# skill_test.net
KiCad netlist of a schematic drawn in EAGLE
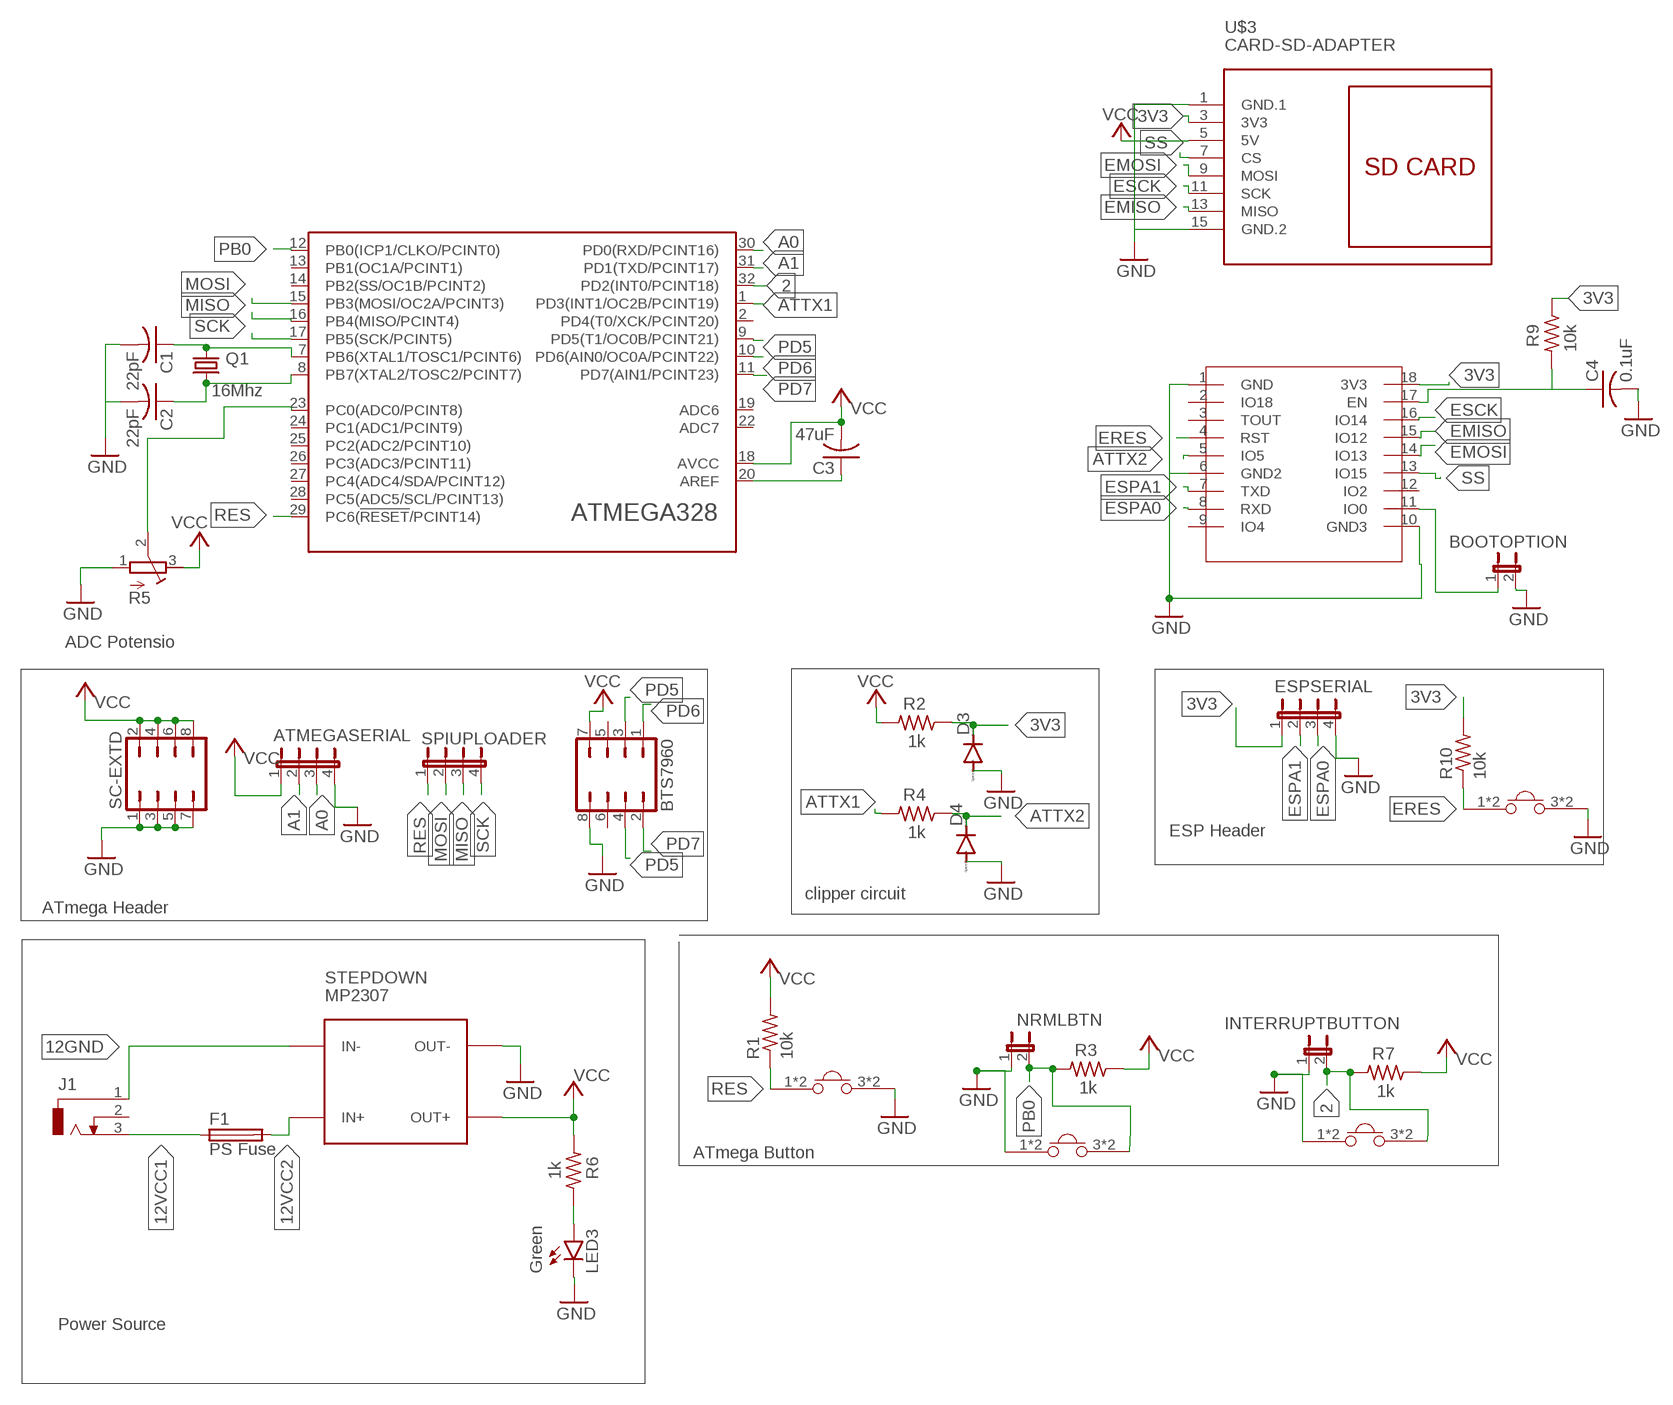
[diagram p0: schematic, sheet 1]

(export (version "E")
  (design (tool "Eeschema 10.0.6"))
  (components
    (comp (ref "2")
      (value "SMD-PUSHBUTTON")
      (footprint "eagle-import:SMD-PUSHBUTTON")
      (libsource (lib "eagle-import") (part "SMD-PUSHBUTTON"))
    )
    (comp (ref "ATMEGA328")
      (value "ATMEGA48/88/168/328-AU")
      (footprint "eagle-import:TQFP32-08")
      (libsource (lib "eagle-import") (part "ATMEGA48/88/168/328-AU"))
    )
    (comp (ref "ATMEGASERIAL")
      (value "JP4E")
      (footprint "eagle-import:JP4")
      (libsource (lib "eagle-import") (part "JP4E"))
    )
    (comp (ref "BOOTOPTION")
      (value "JP1E")
      (footprint "eagle-import:JP1")
      (libsource (lib "eagle-import") (part "JP1E"))
    )
    (comp (ref "BTS7960")
      (value "JP4Q")
      (footprint "eagle-import:JP4Q")
      (libsource (lib "eagle-import") (part "JP4Q"))
    )
    (comp (ref "C1")
      (value "22pF")
      (footprint "eagle-import:C0805")
      (libsource (lib "eagle-import") (part "C-USC0805"))
    )
    (comp (ref "C2")
      (value "22pF")
      (footprint "eagle-import:C0805")
      (libsource (lib "eagle-import") (part "C-USC0805"))
    )
    (comp (ref "C3")
      (value "47uF")
      (footprint "eagle-import:C0805")
      (libsource (lib "eagle-import") (part "C-USC0805"))
    )
    (comp (ref "C4")
      (value "0.1uF")
      (footprint "eagle-import:C025-024X044")
      (libsource (lib "eagle-import") (part "C-US025-024X044"))
    )
    (comp (ref "D3")
      (value "BAT81")
      (footprint "eagle-import:DO34-7")
      (libsource (lib "eagle-import") (part "BAT81"))
    )
    (comp (ref "D4")
      (value "BAT81")
      (footprint "eagle-import:DO34-7")
      (libsource (lib "eagle-import") (part "BAT81"))
    )
    (comp (ref "ESPSERIAL")
      (value "JP4E")
      (footprint "eagle-import:JP4")
      (libsource (lib "eagle-import") (part "JP4E"))
    )
    (comp (ref "F1")
      (value "PS Fuse")
      (footprint "eagle-import:FUSE_HOLDER_5X20MM")
      (libsource (lib "eagle-import") (part "FUSEBLANK_5X20MM"))
    )
    (comp (ref "INTERRUPTBUTTON")
      (value "JP1E")
      (footprint "eagle-import:JP1")
      (libsource (lib "eagle-import") (part "JP1E"))
    )
    (comp (ref "J1")
      (value "DCJ0303")
      (footprint "eagle-import:DCJ0303")
      (libsource (lib "eagle-import") (part "DCJ0303"))
    )
    (comp (ref "LED3")
      (value "Green")
      (footprint "eagle-import:LED3MM")
      (libsource (lib "eagle-import") (part "LED3MM"))
    )
    (comp (ref "NRMLBTN")
      (value "JP1E")
      (footprint "eagle-import:JP1")
      (libsource (lib "eagle-import") (part "JP1E"))
    )
    (comp (ref "PB0")
      (value "SMD-PUSHBUTTON")
      (footprint "eagle-import:SMD-PUSHBUTTON")
      (libsource (lib "eagle-import") (part "SMD-PUSHBUTTON"))
    )
    (comp (ref "Q1")
      (value "16Mhz")
      (footprint "eagle-import:HC49UP")
      (libsource (lib "eagle-import") (part "CRYSTALHC49UP"))
    )
    (comp (ref "R1")
      (value "10k")
      (footprint "eagle-import:R0805")
      (libsource (lib "eagle-import") (part "R-US_R0805"))
    )
    (comp (ref "R2")
      (value "1k")
      (footprint "eagle-import:0204_7")
      (libsource (lib "eagle-import") (part "R-US_0204/7"))
    )
    (comp (ref "R3")
      (value "1k")
      (footprint "eagle-import:0204_7")
      (libsource (lib "eagle-import") (part "R-US_0204/7"))
    )
    (comp (ref "R4")
      (value "1k")
      (footprint "eagle-import:0204_7")
      (libsource (lib "eagle-import") (part "R-US_0204/7"))
    )
    (comp (ref "R5")
      (value "R-TRIMM64W")
      (footprint "eagle-import:RTRIM64W")
      (libsource (lib "eagle-import") (part "R-TRIMM64W"))
    )
    (comp (ref "R6")
      (value "1k")
      (footprint "eagle-import:0204_7")
      (libsource (lib "eagle-import") (part "R-US_0204/7"))
    )
    (comp (ref "R7")
      (value "1k")
      (footprint "eagle-import:0204_7")
      (libsource (lib "eagle-import") (part "R-US_0204/7"))
    )
    (comp (ref "R9")
      (value "10k")
      (footprint "eagle-import:0204_7")
      (libsource (lib "eagle-import") (part "R-US_0204/7"))
    )
    (comp (ref "R10")
      (value "10k")
      (footprint "eagle-import:R0805")
      (libsource (lib "eagle-import") (part "R-US_R0805"))
    )
    (comp (ref "RES")
      (value "SMD-PUSHBUTTON")
      (footprint "eagle-import:SMD-PUSHBUTTON")
      (libsource (lib "eagle-import") (part "SMD-PUSHBUTTON"))
    )
    (comp (ref "SC-EXTD")
      (value "JP4Q")
      (footprint "eagle-import:JP4Q")
      (libsource (lib "eagle-import") (part "JP4Q"))
    )
    (comp (ref "SPIUPLOADER")
      (value "JP4E")
      (footprint "eagle-import:JP4")
      (libsource (lib "eagle-import") (part "JP4E"))
    )
    (comp (ref "STEPDOWN")
      (value "MP2307")
      (footprint "eagle-import:DC-DC-STEP-DOWN-MP2307")
      (libsource (lib "eagle-import") (part "DC-DC-STEP-DOWN-MP2307"))
    )
    (comp (ref "U$1")
      (value "ESP-WROOM-02")
      (footprint "eagle-import:ESP-WROOM-02")
      (libsource (lib "eagle-import") (part "ESP-WROOM-02"))
    )
    (comp (ref "U$3")
      (value "CARD-SD-ADAPTER")
      (footprint "eagle-import:CARD-SD-ADAPTER")
      (libsource (lib "eagle-import") (part "CARD-SD-ADAPTER"))
    )
    (comp (ref "U$6")
      (value "SMD-PUSHBUTTON")
      (footprint "eagle-import:SMD-PUSHBUTTON")
      (libsource (lib "eagle-import") (part "SMD-PUSHBUTTON"))
    )
  )
  (nets
    (net (code "1") (name "2") (class "Default")
      (node (ref "2") (pin "3") (pinfunction "2_3") (pintype "input"))
      (node (ref "2") (pin "4") (pinfunction "2_4") (pintype "input"))
      (node (ref "ATMEGA328") (pin "32") (pinfunction "PD2(INT0/PCINT18)_32") (pintype "bidirectional"))
      (node (ref "INTERRUPTBUTTON") (pin "2") (pinfunction "2_2") (pintype "passive"))
      (node (ref "R7") (pin "2") (pinfunction "2_2") (pintype "passive"))
    )
    (net (code "2") (name "3V3") (class "Default")
      (node (ref "D3") (pin "C") (pinfunction "C_C") (pintype "passive"))
      (node (ref "ESPSERIAL") (pin "1") (pinfunction "1_1") (pintype "passive"))
      (node (ref "R10") (pin "2") (pinfunction "2_2") (pintype "passive"))
      (node (ref "R2") (pin "1") (pinfunction "1_1") (pintype "passive"))
      (node (ref "R9") (pin "1") (pinfunction "1_1") (pintype "passive"))
      (node (ref "U$1") (pin "18") (pinfunction "3V3_18") (pintype "bidirectional"))
      (node (ref "U$3") (pin "3") (pinfunction "3V3_3") (pintype "power_in"))
    )
    (net (code "3") (name "12GND") (class "Default")
      (node (ref "J1") (pin "1") (pinfunction "1_1") (pintype "passive"))
      (node (ref "STEPDOWN") (pin "IN-") (pinfunction "IN-_IN-") (pintype "bidirectional"))
    )
    (net (code "4") (name "12VCC1") (class "Default")
      (node (ref "F1") (pin "1") (pinfunction "1_1") (pintype "passive"))
      (node (ref "J1") (pin "3") (pinfunction "3_3") (pintype "passive"))
    )
    (net (code "5") (name "12VCC2") (class "Default")
      (node (ref "F1") (pin "2") (pinfunction "2_2") (pintype "passive"))
      (node (ref "STEPDOWN") (pin "IN+") (pinfunction "IN+_IN+") (pintype "bidirectional"))
    )
    (net (code "6") (name "A0") (class "Default")
      (node (ref "ATMEGA328") (pin "30") (pinfunction "PD0(RXD/PCINT16)_30") (pintype "bidirectional"))
      (node (ref "ATMEGASERIAL") (pin "3") (pinfunction "3_3") (pintype "passive"))
    )
    (net (code "7") (name "A1") (class "Default")
      (node (ref "ATMEGA328") (pin "31") (pinfunction "PD1(TXD/PCINT17)_31") (pintype "bidirectional"))
      (node (ref "ATMEGASERIAL") (pin "2") (pinfunction "2_2") (pintype "passive"))
    )
    (net (code "8") (name "ATTX1") (class "Default")
      (node (ref "ATMEGA328") (pin "1") (pinfunction "PD3(INT1/OC2B/PCINT19)_1") (pintype "bidirectional"))
      (node (ref "R4") (pin "2") (pinfunction "2_2") (pintype "passive"))
    )
    (net (code "9") (name "ATTX2") (class "Default")
      (node (ref "D4") (pin "C") (pinfunction "C_C") (pintype "passive"))
      (node (ref "R4") (pin "1") (pinfunction "1_1") (pintype "passive"))
      (node (ref "U$1") (pin "5") (pinfunction "IO5_5") (pintype "bidirectional"))
    )
    (net (code "10") (name "EMISO") (class "Default")
      (node (ref "U$1") (pin "15") (pinfunction "IO12_15") (pintype "bidirectional"))
      (node (ref "U$3") (pin "13") (pinfunction "MISO_13") (pintype "bidirectional"))
    )
    (net (code "11") (name "EMOSI") (class "Default")
      (node (ref "U$1") (pin "14") (pinfunction "IO13_14") (pintype "bidirectional"))
      (node (ref "U$3") (pin "9") (pinfunction "MOSI_9") (pintype "bidirectional"))
    )
    (net (code "12") (name "ERES") (class "Default")
      (node (ref "R10") (pin "1") (pinfunction "1_1") (pintype "passive"))
      (node (ref "U$1") (pin "4") (pinfunction "RST_4") (pintype "bidirectional"))
      (node (ref "U$6") (pin "1") (pinfunction "1_1") (pintype "input"))
      (node (ref "U$6") (pin "2") (pinfunction "1_2") (pintype "input"))
    )
    (net (code "13") (name "ESCK") (class "Default")
      (node (ref "U$1") (pin "16") (pinfunction "IO14_16") (pintype "bidirectional"))
      (node (ref "U$3") (pin "11") (pinfunction "SCK_11") (pintype "bidirectional"))
    )
    (net (code "14") (name "ESPA0") (class "Default")
      (node (ref "ESPSERIAL") (pin "3") (pinfunction "3_3") (pintype "passive"))
      (node (ref "U$1") (pin "8") (pinfunction "RXD_8") (pintype "bidirectional"))
    )
    (net (code "15") (name "ESPA1") (class "Default")
      (node (ref "ESPSERIAL") (pin "2") (pinfunction "2_2") (pintype "passive"))
      (node (ref "U$1") (pin "7") (pinfunction "TXD_7") (pintype "bidirectional"))
    )
    (net (code "16") (name "GND") (class "Default")
      (node (ref "2") (pin "1") (pinfunction "1_1") (pintype "input"))
      (node (ref "2") (pin "2") (pinfunction "1_2") (pintype "input"))
      (node (ref "ATMEGASERIAL") (pin "4") (pinfunction "4_4") (pintype "passive"))
      (node (ref "BOOTOPTION") (pin "2") (pinfunction "2_2") (pintype "passive"))
      (node (ref "BTS7960") (pin "8") (pinfunction "8_8") (pintype "passive"))
      (node (ref "C1") (pin "2") (pinfunction "2_2") (pintype "passive"))
      (node (ref "C2") (pin "2") (pinfunction "2_2") (pintype "passive"))
      (node (ref "C4") (pin "2") (pinfunction "2_2") (pintype "passive"))
      (node (ref "D3") (pin "A") (pinfunction "A_A") (pintype "passive"))
      (node (ref "D4") (pin "A") (pinfunction "A_A") (pintype "passive"))
      (node (ref "ESPSERIAL") (pin "4") (pinfunction "4_4") (pintype "passive"))
      (node (ref "INTERRUPTBUTTON") (pin "1") (pinfunction "1_1") (pintype "passive"))
      (node (ref "LED3") (pin "K") (pinfunction "C_K") (pintype "passive"))
      (node (ref "NRMLBTN") (pin "1") (pinfunction "1_1") (pintype "passive"))
      (node (ref "PB0") (pin "1") (pinfunction "1_1") (pintype "input"))
      (node (ref "PB0") (pin "2") (pinfunction "1_2") (pintype "input"))
      (node (ref "R5") (pin "1") (pinfunction "A_1") (pintype "passive"))
      (node (ref "RES") (pin "3") (pinfunction "2_3") (pintype "input"))
      (node (ref "RES") (pin "4") (pinfunction "2_4") (pintype "input"))
      (node (ref "SC-EXTD") (pin "1") (pinfunction "1_1") (pintype "passive"))
      (node (ref "SC-EXTD") (pin "3") (pinfunction "3_3") (pintype "passive"))
      (node (ref "SC-EXTD") (pin "5") (pinfunction "5_5") (pintype "passive"))
      (node (ref "SC-EXTD") (pin "7") (pinfunction "7_7") (pintype "passive"))
      (node (ref "STEPDOWN") (pin "OUT-") (pinfunction "OUT-_OUT-") (pintype "bidirectional"))
      (node (ref "U$1") (pin "1") (pinfunction "GND_1") (pintype "bidirectional"))
      (node (ref "U$1") (pin "10") (pinfunction "GND3_10") (pintype "bidirectional"))
      (node (ref "U$1") (pin "6") (pinfunction "GND2_6") (pintype "bidirectional"))
      (node (ref "U$3") (pin "1") (pinfunction "GND.1_1") (pintype "power_in"))
      (node (ref "U$3") (pin "15") (pinfunction "GND.2_15") (pintype "power_in"))
      (node (ref "U$6") (pin "3") (pinfunction "2_3") (pintype "input"))
      (node (ref "U$6") (pin "4") (pinfunction "2_4") (pintype "input"))
    )
    (net (code "17") (name "MISO") (class "Default")
      (node (ref "ATMEGA328") (pin "16") (pinfunction "PB4(MISO/PCINT4)_16") (pintype "bidirectional"))
      (node (ref "SPIUPLOADER") (pin "3") (pinfunction "3_3") (pintype "passive"))
    )
    (net (code "18") (name "MOSI") (class "Default")
      (node (ref "ATMEGA328") (pin "15") (pinfunction "PB3(MOSI/OC2A/PCINT3)_15") (pintype "bidirectional"))
      (node (ref "SPIUPLOADER") (pin "2") (pinfunction "2_2") (pintype "passive"))
    )
    (net (code "19") (name "Net-(ATMEGA328A-AREF)") (class "Default")
      (node (ref "ATMEGA328") (pin "20") (pinfunction "AREF_20") (pintype "passive"))
      (node (ref "C3") (pin "1") (pinfunction "1_1") (pintype "passive"))
    )
    (net (code "20") (name "Net-(ATMEGA328A-PB6(XTAL1{slash}TOSC1{slash}PCINT6))") (class "Default")
      (node (ref "ATMEGA328") (pin "7") (pinfunction "PB6(XTAL1/TOSC1/PCINT6)_7") (pintype "bidirectional"))
      (node (ref "C1") (pin "1") (pinfunction "1_1") (pintype "passive"))
      (node (ref "Q1") (pin "1") (pinfunction "1_1") (pintype "passive"))
    )
    (net (code "21") (name "Net-(ATMEGA328A-PB7(XTAL2{slash}TOSC2{slash}PCINT7))") (class "Default")
      (node (ref "ATMEGA328") (pin "8") (pinfunction "PB7(XTAL2/TOSC2/PCINT7)_8") (pintype "bidirectional"))
      (node (ref "C2") (pin "1") (pinfunction "1_1") (pintype "passive"))
      (node (ref "Q1") (pin "2") (pinfunction "2_2") (pintype "passive"))
    )
    (net (code "22") (name "Net-(ATMEGA328A-PC0(ADC0{slash}PCINT8))") (class "Default")
      (node (ref "ATMEGA328") (pin "23") (pinfunction "PC0(ADC0/PCINT8)_23") (pintype "bidirectional"))
      (node (ref "R5") (pin "2") (pinfunction "S_2") (pintype "passive"))
    )
    (net (code "23") (name "Net-(LED3-PadA)") (class "Default")
      (node (ref "LED3") (pin "A") (pinfunction "A_A") (pintype "passive"))
      (node (ref "R6") (pin "1") (pinfunction "1_1") (pintype "passive"))
    )
    (net (code "24") (name "Net-(U$1-EN)") (class "Default")
      (node (ref "C4") (pin "1") (pinfunction "1_1") (pintype "passive"))
      (node (ref "R9") (pin "2") (pinfunction "2_2") (pintype "passive"))
      (node (ref "U$1") (pin "17") (pinfunction "EN_17") (pintype "bidirectional"))
    )
    (net (code "25") (name "Net-(U$1-IO0)") (class "Default")
      (node (ref "BOOTOPTION") (pin "1") (pinfunction "1_1") (pintype "passive"))
      (node (ref "U$1") (pin "11") (pinfunction "IO0_11") (pintype "bidirectional"))
    )
    (net (code "26") (name "PB0") (class "Default")
      (node (ref "ATMEGA328") (pin "12") (pinfunction "PB0(ICP1/CLKO/PCINT0)_12") (pintype "bidirectional"))
      (node (ref "NRMLBTN") (pin "2") (pinfunction "2_2") (pintype "passive"))
      (node (ref "PB0") (pin "3") (pinfunction "2_3") (pintype "input"))
      (node (ref "PB0") (pin "4") (pinfunction "2_4") (pintype "input"))
      (node (ref "R3") (pin "2") (pinfunction "2_2") (pintype "passive"))
    )
    (net (code "27") (name "PD5") (class "Default")
      (node (ref "ATMEGA328") (pin "9") (pinfunction "PD5(T1/OC0B/PCINT21)_9") (pintype "bidirectional"))
      (node (ref "BTS7960") (pin "3") (pinfunction "3_3") (pintype "passive"))
      (node (ref "BTS7960") (pin "4") (pinfunction "4_4") (pintype "passive"))
    )
    (net (code "28") (name "PD6") (class "Default")
      (node (ref "ATMEGA328") (pin "10") (pinfunction "PD6(AIN0/OC0A/PCINT22)_10") (pintype "bidirectional"))
      (node (ref "BTS7960") (pin "1") (pinfunction "1_1") (pintype "passive"))
    )
    (net (code "29") (name "PD7") (class "Default")
      (node (ref "ATMEGA328") (pin "11") (pinfunction "PD7(AIN1/PCINT23)_11") (pintype "bidirectional"))
      (node (ref "BTS7960") (pin "2") (pinfunction "2_2") (pintype "passive"))
    )
    (net (code "30") (name "RES") (class "Default")
      (node (ref "ATMEGA328") (pin "29") (pinfunction "PC6(~{RESET}/PCINT14)_29") (pintype "bidirectional"))
      (node (ref "R1") (pin "1") (pinfunction "1_1") (pintype "passive"))
      (node (ref "RES") (pin "1") (pinfunction "1_1") (pintype "input"))
      (node (ref "RES") (pin "2") (pinfunction "1_2") (pintype "input"))
      (node (ref "SPIUPLOADER") (pin "1") (pinfunction "1_1") (pintype "passive"))
    )
    (net (code "31") (name "SCK") (class "Default")
      (node (ref "ATMEGA328") (pin "17") (pinfunction "PB5(SCK/PCINT5)_17") (pintype "bidirectional"))
      (node (ref "SPIUPLOADER") (pin "4") (pinfunction "4_4") (pintype "passive"))
    )
    (net (code "32") (name "SS") (class "Default")
      (node (ref "U$1") (pin "13") (pinfunction "IO15_13") (pintype "bidirectional"))
      (node (ref "U$3") (pin "7") (pinfunction "CS_7") (pintype "bidirectional"))
    )
    (net (code "33") (name "VCC") (class "Default")
      (node (ref "ATMEGA328") (pin "18") (pinfunction "AVCC_18") (pintype "power_in"))
      (node (ref "ATMEGASERIAL") (pin "1") (pinfunction "1_1") (pintype "passive"))
      (node (ref "BTS7960") (pin "7") (pinfunction "7_7") (pintype "passive"))
      (node (ref "C3") (pin "2") (pinfunction "2_2") (pintype "passive"))
      (node (ref "R1") (pin "2") (pinfunction "2_2") (pintype "passive"))
      (node (ref "R2") (pin "2") (pinfunction "2_2") (pintype "passive"))
      (node (ref "R3") (pin "1") (pinfunction "1_1") (pintype "passive"))
      (node (ref "R5") (pin "3") (pinfunction "E_3") (pintype "passive"))
      (node (ref "R6") (pin "2") (pinfunction "2_2") (pintype "passive"))
      (node (ref "R7") (pin "1") (pinfunction "1_1") (pintype "passive"))
      (node (ref "SC-EXTD") (pin "2") (pinfunction "2_2") (pintype "passive"))
      (node (ref "SC-EXTD") (pin "4") (pinfunction "4_4") (pintype "passive"))
      (node (ref "SC-EXTD") (pin "6") (pinfunction "6_6") (pintype "passive"))
      (node (ref "SC-EXTD") (pin "8") (pinfunction "8_8") (pintype "passive"))
      (node (ref "STEPDOWN") (pin "OUT+") (pinfunction "OUT+_OUT+") (pintype "bidirectional"))
      (node (ref "U$3") (pin "5") (pinfunction "5V_5") (pintype "power_in"))
    )
    (net (code "34") (name "unconnected-(ATMEGA328A-ADC6-Pad19)") (class "Default")
      (node (ref "ATMEGA328") (pin "19") (pinfunction "ADC6_19") (pintype "passive"))
    )
    (net (code "35") (name "unconnected-(ATMEGA328A-ADC7-Pad22)") (class "Default")
      (node (ref "ATMEGA328") (pin "22") (pinfunction "ADC7_22") (pintype "passive"))
    )
    (net (code "36") (name "unconnected-(ATMEGA328A-PB1(OC1A{slash}PCINT1)-Pad13)") (class "Default")
      (node (ref "ATMEGA328") (pin "13") (pinfunction "PB1(OC1A/PCINT1)_13") (pintype "bidirectional"))
    )
    (net (code "37") (name "unconnected-(ATMEGA328A-PB2(SS{slash}OC1B{slash}PCINT2)-Pad14)") (class "Default")
      (node (ref "ATMEGA328") (pin "14") (pinfunction "PB2(SS/OC1B/PCINT2)_14") (pintype "bidirectional"))
    )
    (net (code "38") (name "unconnected-(ATMEGA328A-PC1(ADC1{slash}PCINT9)-Pad24)") (class "Default")
      (node (ref "ATMEGA328") (pin "24") (pinfunction "PC1(ADC1/PCINT9)_24") (pintype "bidirectional"))
    )
    (net (code "39") (name "unconnected-(ATMEGA328A-PC2(ADC2{slash}PCINT10)-Pad25)") (class "Default")
      (node (ref "ATMEGA328") (pin "25") (pinfunction "PC2(ADC2/PCINT10)_25") (pintype "bidirectional"))
    )
    (net (code "40") (name "unconnected-(ATMEGA328A-PC3(ADC3{slash}PCINT11)-Pad26)") (class "Default")
      (node (ref "ATMEGA328") (pin "26") (pinfunction "PC3(ADC3/PCINT11)_26") (pintype "bidirectional"))
    )
    (net (code "41") (name "unconnected-(ATMEGA328A-PC4(ADC4{slash}SDA{slash}PCINT12)-Pad27)") (class "Default")
      (node (ref "ATMEGA328") (pin "27") (pinfunction "PC4(ADC4/SDA/PCINT12)_27") (pintype "bidirectional"))
    )
    (net (code "42") (name "unconnected-(ATMEGA328A-PC5(ADC5{slash}SCL{slash}PCINT13)-Pad28)") (class "Default")
      (node (ref "ATMEGA328") (pin "28") (pinfunction "PC5(ADC5/SCL/PCINT13)_28") (pintype "bidirectional"))
    )
    (net (code "43") (name "unconnected-(ATMEGA328A-PD4(T0{slash}XCK{slash}PCINT20)-Pad2)") (class "Default")
      (node (ref "ATMEGA328") (pin "2") (pinfunction "PD4(T0/XCK/PCINT20)_2") (pintype "bidirectional"))
    )
    (net (code "44") (name "unconnected-(BTS7960-Pad5)") (class "Default")
      (node (ref "BTS7960") (pin "5") (pinfunction "5_5") (pintype "passive"))
    )
    (net (code "45") (name "unconnected-(BTS7960-Pad6)") (class "Default")
      (node (ref "BTS7960") (pin "6") (pinfunction "6_6") (pintype "passive"))
    )
    (net (code "46") (name "unconnected-(J1-Pad2)") (class "Default")
      (node (ref "J1") (pin "2") (pinfunction "2_2") (pintype "passive"))
    )
    (net (code "47") (name "unconnected-(U$1-IO2-Pad12)") (class "Default")
      (node (ref "U$1") (pin "12") (pinfunction "IO2_12") (pintype "bidirectional"))
    )
    (net (code "48") (name "unconnected-(U$1-IO4-Pad9)") (class "Default")
      (node (ref "U$1") (pin "9") (pinfunction "IO4_9") (pintype "bidirectional"))
    )
    (net (code "49") (name "unconnected-(U$1-IO18-Pad2)") (class "Default")
      (node (ref "U$1") (pin "2") (pinfunction "IO18_2") (pintype "bidirectional"))
    )
    (net (code "50") (name "unconnected-(U$1-TOUT-Pad3)") (class "Default")
      (node (ref "U$1") (pin "3") (pinfunction "TOUT_3") (pintype "bidirectional"))
    )
  )
)
